# Mini_System.net
KiCad netlist of a schematic drawn in Altium Designer
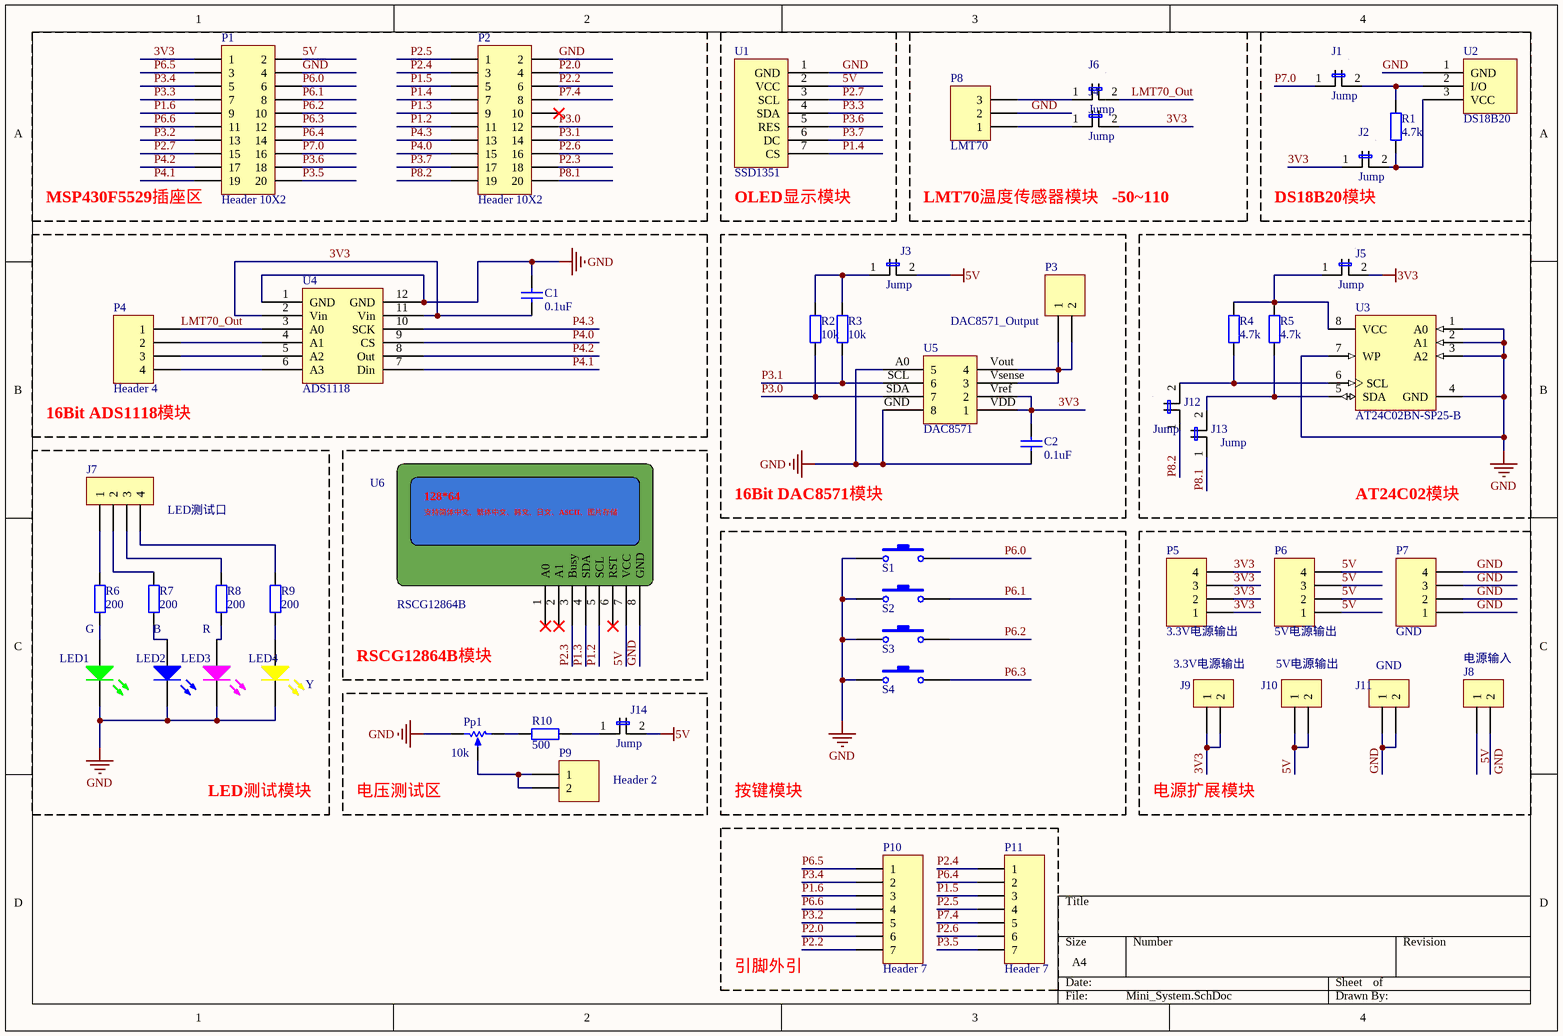
[diagram p0: Mini_System.SchDoc]

(export (version "E")
  (design (tool "Eeschema 10.0.6"))
  (components
    (comp (ref "C1")
      (value "0.1uF")
      (footprint "Capacitor-Disk-Middle")
      (description "CBB聚乙烯薄膜电容")
      (fields (field (name "VOLTAGE") "63V") (field (name "PUBLISHER") "Altium Limited"))
      (libsource (lib "02-Miscellaneous_Devices_ZSF_Library") (part "Cap Nicklon"))
    )
    (comp (ref "C2")
      (value "0.1uF")
      (footprint "Capacitor-Disk-Middle")
      (description "CBB聚乙烯薄膜电容")
      (fields (field (name "VOLTAGE") "63V") (field (name "PUBLISHER") "Altium Limited"))
      (libsource (lib "02-Miscellaneous_Devices_ZSF_Library") (part "Cap Nicklon"))
    )
    (comp (ref "J1") (value "Jump") (footprint "HDR-1x2") (libsource (lib "Mini_System") (part "Jump")))
    (comp (ref "J2") (value "Jump") (footprint "HDR-1x2") (libsource (lib "Mini_System") (part "Jump")))
    (comp (ref "J3") (value "Jump") (footprint "HDR-1x2") (libsource (lib "Mini_System") (part "Jump")))
    (comp (ref "J4") (value "Jump") (footprint "HDR-1x2") (libsource (lib "Mini_System") (part "Jump")))
    (comp (ref "J5") (value "Jump") (footprint "HDR-1x2") (libsource (lib "Mini_System") (part "Jump")))
    (comp (ref "J6") (value "Jump") (footprint "HDR-1x2") (libsource (lib "Mini_System") (part "Jump")))
    (comp (ref "J7")
      (value "LED测试口")
      (footprint "HDR-1X4_M")
      (description "排针")
      (libsource (lib "Connector") (part "HDR1X4"))
    )
    (comp (ref "J8")
      (value "电源输入")
      (footprint "Connector:XH2.54-2P")
      (description "连接器")
      (libsource (lib "Connector") (part "CON2"))
    )
    (comp (ref "J9")
      (value "3.3V电源输出")
      (footprint "Connector:WJ500V-5.08-2")
      (description "接线端子")
      (libsource (lib "Connector") (part "KF128-5.08MM-2P"))
    )
    (comp (ref "J10")
      (value "5V电源输出")
      (footprint "Connector:WJ500V-5.08-2")
      (description "接线端子")
      (libsource (lib "Connector") (part "KF128-5.08MM-2P"))
    )
    (comp (ref "J11")
      (value "GND")
      (footprint "Connector:WJ500V-5.08-2")
      (description "接线端子")
      (libsource (lib "Connector") (part "KF128-5.08MM-2P"))
    )
    (comp (ref "J12") (value "Jump") (footprint "HDR-1x2") (libsource (lib "Mini_System") (part "Jump")))
    (comp (ref "J13") (value "Jump") (footprint "HDR-1x2") (libsource (lib "Mini_System") (part "Jump")))
    (comp (ref "J14") (value "Jump") (footprint "HDR-1x2") (libsource (lib "Mini_System") (part "Jump")))
    (comp (ref "LED1")
      (value "G")
      (footprint "LED-R3-H5-SINGLE-G")
      (description "Typical INFRARED GaAs LED")
      (fields (field (name "PUBLISHER") "Altium Limited"))
      (libsource (lib "03-EButterflyIntegratedLibrary") (part "LED-3-G"))
    )
    (comp (ref "LED2")
      (value "B")
      (footprint "LED-R3-H5-SINGLE-B")
      (description "Typical INFRARED GaAs LED")
      (fields (field (name "PUBLISHER") "Altium Limited"))
      (libsource (lib "03-EButterflyIntegratedLibrary") (part "LED-3-B"))
    )
    (comp (ref "LED3")
      (value "R")
      (footprint "LED-R3-H5-SINGLE-R")
      (description "Typical INFRARED GaAs LED")
      (fields (field (name "PUBLISHER") "Altium Limited"))
      (libsource (lib "03-EButterflyIntegratedLibrary") (part "LED-3-R"))
    )
    (comp (ref "LED4")
      (value "Y")
      (footprint "LED-R3-H5-SINGLE-Y")
      (description "Typical INFRARED GaAs LED")
      (fields (field (name "PUBLISHER") "Altium Limited"))
      (libsource (lib "03-EButterflyIntegratedLibrary") (part "LED-3-Y"))
    )
    (comp (ref "P1")
      (value "Header 10X2")
      (footprint "HDR2X10")
      (description "Header, 10-Pin, Dual row")
      (fields (field (name "PUBLISHER") "Altium Limited"))
      (libsource (lib "03-EButterflyIntegratedLibrary") (part "Header 10X2"))
    )
    (comp (ref "P2")
      (value "Header 10X2")
      (footprint "HDR2X10")
      (description "Header, 10-Pin, Dual row")
      (fields (field (name "PUBLISHER") "Altium Limited"))
      (libsource (lib "03-EButterflyIntegratedLibrary") (part "Header 10X2"))
    )
    (comp (ref "P3")
      (value "DAC8571_Output")
      (footprint "HDR-1X2_H")
      (description "Header, 2-Pin")
      (fields (field (name "PUBLISHER") "Altium Limited"))
      (libsource (lib "") (part "Header 2_1"))
    )
    (comp (ref "P4")
      (value "Header 4")
      (footprint "HDR1X4")
      (description "Header, 4-Pin")
      (fields (field (name "PUBLISHER") "Altium Limited"))
      (libsource (lib "") (part "Header 4_1"))
    )
    (comp (ref "P5")
      (value "3.3V电源输出")
      (footprint "HDR1X4")
      (description "Header, 4-Pin")
      (fields (field (name "PUBLISHER") "Altium Limited"))
      (libsource (lib "03-EButterflyIntegratedLibrary") (part "Header 4"))
    )
    (comp (ref "P6")
      (value "5V电源输出")
      (footprint "HDR1X4")
      (description "Header, 4-Pin")
      (fields (field (name "PUBLISHER") "Altium Limited"))
      (libsource (lib "03-EButterflyIntegratedLibrary") (part "Header 4"))
    )
    (comp (ref "P7")
      (value "GND")
      (footprint "HDR1X4")
      (description "Header, 4-Pin")
      (fields (field (name "PUBLISHER") "Altium Limited"))
      (libsource (lib "03-EButterflyIntegratedLibrary") (part "Header 4"))
    )
    (comp (ref "P8")
      (value "LMT70")
      (footprint "HDR-1X3_M")
      (description "Header, 3-Pin")
      (fields (field (name "PUBLISHER") "Altium Limited"))
      (libsource (lib "03-EButterflyIntegratedLibrary") (part "Header 3"))
    )
    (comp (ref "P9")
      (value "Header 2")
      (footprint "HDR1X2")
      (description "Header, 2-Pin")
      (fields (field (name "PUBLISHER") "Altium Limited"))
      (libsource (lib "03-EButterflyIntegratedLibrary") (part "Header 2"))
    )
    (comp (ref "P10")
      (value "Header 7")
      (footprint "HDR-1X7_M")
      (description "Header, 7-Pin")
      (fields (field (name "PUBLISHER") "Altium Limited"))
      (libsource (lib "Miscellaneous Connectors") (part "Header 7"))
    )
    (comp (ref "P11")
      (value "Header 7")
      (footprint "HDR-1X7_M")
      (description "Header, 7-Pin")
      (fields (field (name "PUBLISHER") "Altium Limited"))
      (libsource (lib "Miscellaneous Connectors") (part "Header 7"))
    )
    (comp (ref "Pp1")
      (value "10k")
      (footprint "RP_3296")
      (description "3296电位器")
      (libsource (lib "02-Miscellaneous_Devices_ZSF_Library") (part "RP_3296"))
    )
    (comp (ref "R1")
      (value "4.7k")
      (footprint "Resistors:RS 1/4W")
      (description "Resistor")
      (fields (field (name "PUBLISHER") "Altium Limited"))
      (libsource (lib "Miscellaneous Devices") (part "Res2"))
    )
    (comp (ref "R2")
      (value "10k")
      (footprint "Resistors:RS 1/4W")
      (description "Resistor")
      (fields (field (name "PUBLISHER") "Altium Limited"))
      (libsource (lib "Miscellaneous Devices") (part "Res2"))
    )
    (comp (ref "R3")
      (value "10k")
      (footprint "Resistors:RS 1/4W")
      (description "Resistor")
      (fields (field (name "PUBLISHER") "Altium Limited"))
      (libsource (lib "Miscellaneous Devices") (part "Res2"))
    )
    (comp (ref "R4")
      (value "4.7k")
      (footprint "Resistors:RS 1/4W")
      (description "Resistor")
      (fields (field (name "PUBLISHER") "Altium Limited"))
      (libsource (lib "Miscellaneous Devices") (part "Res2"))
    )
    (comp (ref "R5")
      (value "4.7k")
      (footprint "Resistors:RS 1/4W")
      (description "Resistor")
      (fields (field (name "PUBLISHER") "Altium Limited"))
      (libsource (lib "Miscellaneous Devices") (part "Res2"))
    )
    (comp (ref "R6")
      (value "200")
      (footprint "Resistors:RS 1/4W")
      (description "Resistor")
      (fields (field (name "PUBLISHER") "Altium Limited"))
      (libsource (lib "Miscellaneous Devices") (part "Res2"))
    )
    (comp (ref "R7")
      (value "200")
      (footprint "Resistors:RS 1/4W")
      (description "Resistor")
      (fields (field (name "PUBLISHER") "Altium Limited"))
      (libsource (lib "Miscellaneous Devices") (part "Res2"))
    )
    (comp (ref "R8")
      (value "200")
      (footprint "Resistors:RS 1/4W")
      (description "Resistor")
      (fields (field (name "PUBLISHER") "Altium Limited"))
      (libsource (lib "Miscellaneous Devices") (part "Res2"))
    )
    (comp (ref "R9")
      (value "200")
      (footprint "Resistors:RS 1/4W")
      (description "Resistor")
      (fields (field (name "PUBLISHER") "Altium Limited"))
      (libsource (lib "Miscellaneous Devices") (part "Res2"))
    )
    (comp (ref "R10")
      (value "500")
      (footprint "Resistors:RS 1/4W")
      (description "Resistor")
      (fields (field (name "PUBLISHER") "Altium Limited"))
      (libsource (lib "") (part "Res2_1"))
    )
    (comp (ref "S1")
      (value "S1")
      (footprint "BUTTON_6*6")
      (description "Tactile Switch触觉开关")
      (fields (field (name "PUBLISHER") "Altium Limited"))
      (libsource (lib "02-Miscellaneous_Devices_ZSF_Library") (part "SW-PB"))
    )
    (comp (ref "S2")
      (value "S2")
      (footprint "BUTTON_6*6")
      (description "Tactile Switch触觉开关")
      (fields (field (name "PUBLISHER") "Altium Limited"))
      (libsource (lib "02-Miscellaneous_Devices_ZSF_Library") (part "SW-PB"))
    )
    (comp (ref "S3")
      (value "S3")
      (footprint "BUTTON_6*6")
      (description "Tactile Switch触觉开关")
      (fields (field (name "PUBLISHER") "Altium Limited"))
      (libsource (lib "02-Miscellaneous_Devices_ZSF_Library") (part "SW-PB"))
    )
    (comp (ref "S4")
      (value "S4")
      (footprint "BUTTON_6*6")
      (description "Tactile Switch触觉开关")
      (fields (field (name "PUBLISHER") "Altium Limited"))
      (libsource (lib "02-Miscellaneous_Devices_ZSF_Library") (part "SW-PB"))
    )
    (comp (ref "U1")
      (value "SSD1351")
      (footprint "HDR-1X7_M")
      (description "1.5寸彩色OLED")
      (libsource (lib "Mini_System") (part "1.5'OLED RGB SSD1351"))
    )
    (comp (ref "U2")
      (value "DS18B20")
      (footprint "HDR-1X3_Y")
      (libsource (lib "02-Miscellaneous_Devices_ZSF_Library") (part "DS18B20"))
    )
    (comp (ref "U3")
      (value "AT24C02BN-SP25-B")
      (footprint "DIP8-300_MH")
      (fields (field (name "PUBLISHER") "Altium Limited"))
      (libsource (lib "altium-import") (part "root_0_mirrored_AT24C02BN-SP25-B_"))
    )
    (comp (ref "U4")
      (value "ADS1118")
      (footprint "dip12")
      (description "16位ADC芯片，将模拟电压信号转化为数字信号供单片机处理")
      (libsource (lib "Mini_System") (part "ADS1118"))
    )
    (comp (ref "U5")
      (value "DAC8571")
      (footprint "DIP8-300_MH")
      (description "16位DAC芯片，将数字量转化为模拟电压输出")
      (libsource (lib "Mini_System") (part "DAC8571"))
    )
    (comp (ref "U6")
      (value "RSCG12864B")
      (footprint "HDR-1X8_M")
      (libsource (lib "Mini_System") (part "RSCG12864B"))
    )
  )
  (nets
    (net (code "1") (name "/LMT70_Out") (class "Default")
      (node (ref "J6") (pin "2") (pinfunction "2_2") (pintype "passive"))
      (node (ref "P4") (pin "1") (pinfunction "1_1") (pintype "passive"))
      (node (ref "U4") (pin "3") (pinfunction "A0_3") (pintype "passive"))
    )
    (net (code "2") (name "/P1.2") (class "Default")
      (node (ref "P2") (pin "11") (pinfunction "11_11") (pintype "passive"))
      (node (ref "U6") (pin "5") (pinfunction "SCL_5") (pintype "passive"))
    )
    (net (code "3") (name "/P1.3") (class "Default")
      (node (ref "P2") (pin "9") (pinfunction "9_9") (pintype "passive"))
      (node (ref "U6") (pin "4") (pinfunction "SDA_4") (pintype "passive"))
    )
    (net (code "4") (name "/P1.4") (class "Default")
      (node (ref "P2") (pin "7") (pinfunction "7_7") (pintype "passive"))
      (node (ref "U1") (pin "7") (pinfunction "CS_7") (pintype "passive"))
    )
    (net (code "5") (name "/P1.5") (class "Default")
      (node (ref "P11") (pin "3") (pinfunction "3_3") (pintype "passive"))
      (node (ref "P2") (pin "5") (pinfunction "5_5") (pintype "passive"))
    )
    (net (code "6") (name "/P1.6") (class "Default")
      (node (ref "P1") (pin "9") (pinfunction "9_9") (pintype "passive"))
      (node (ref "P10") (pin "3") (pinfunction "3_3") (pintype "passive"))
    )
    (net (code "7") (name "/P2.0") (class "Default")
      (node (ref "P10") (pin "6") (pinfunction "6_6") (pintype "passive"))
      (node (ref "P2") (pin "4") (pinfunction "4_4") (pintype "passive"))
    )
    (net (code "8") (name "/P2.2") (class "Default")
      (node (ref "P10") (pin "7") (pinfunction "7_7") (pintype "passive"))
      (node (ref "P2") (pin "6") (pinfunction "6_6") (pintype "passive"))
    )
    (net (code "9") (name "/P2.3") (class "Default")
      (node (ref "P2") (pin "18") (pinfunction "18_18") (pintype "passive"))
      (node (ref "U6") (pin "3") (pinfunction "Busy_3") (pintype "passive"))
    )
    (net (code "10") (name "/P2.4") (class "Default")
      (node (ref "P11") (pin "1") (pinfunction "1_1") (pintype "passive"))
      (node (ref "P2") (pin "3") (pinfunction "3_3") (pintype "passive"))
    )
    (net (code "11") (name "/P2.5") (class "Default")
      (node (ref "P11") (pin "4") (pinfunction "4_4") (pintype "passive"))
      (node (ref "P2") (pin "1") (pinfunction "1_1") (pintype "passive"))
    )
    (net (code "12") (name "/P2.6") (class "Default")
      (node (ref "P11") (pin "6") (pinfunction "6_6") (pintype "passive"))
      (node (ref "P2") (pin "16") (pinfunction "16_16") (pintype "passive"))
    )
    (net (code "13") (name "/P2.7") (class "Default")
      (node (ref "P1") (pin "15") (pinfunction "15_15") (pintype "passive"))
      (node (ref "U1") (pin "3") (pinfunction "SCL_3") (pintype "passive"))
    )
    (net (code "14") (name "/P3.0") (class "Default")
      (node (ref "P2") (pin "12") (pinfunction "12_12") (pintype "passive"))
      (node (ref "R2") (pin "1") (pinfunction "1_1") (pintype "passive"))
      (node (ref "U5") (pin "SDA") (pinfunction "7_SDA") (pintype "passive"))
    )
    (net (code "15") (name "/P3.1") (class "Default")
      (node (ref "P2") (pin "14") (pinfunction "14_14") (pintype "passive"))
      (node (ref "R3") (pin "1") (pinfunction "1_1") (pintype "passive"))
      (node (ref "U5") (pin "SCL") (pinfunction "6_SCL") (pintype "passive"))
    )
    (net (code "16") (name "/P3.2") (class "Default")
      (node (ref "P1") (pin "13") (pinfunction "13_13") (pintype "passive"))
      (node (ref "P10") (pin "5") (pinfunction "5_5") (pintype "passive"))
    )
    (net (code "17") (name "/P3.3") (class "Default")
      (node (ref "P1") (pin "7") (pinfunction "7_7") (pintype "passive"))
      (node (ref "U1") (pin "4") (pinfunction "SDA_4") (pintype "passive"))
    )
    (net (code "18") (name "/P3.4") (class "Default")
      (node (ref "P1") (pin "5") (pinfunction "5_5") (pintype "passive"))
      (node (ref "P10") (pin "2") (pinfunction "2_2") (pintype "passive"))
    )
    (net (code "19") (name "/P3.5") (class "Default")
      (node (ref "P1") (pin "20") (pinfunction "20_20") (pintype "passive"))
      (node (ref "P11") (pin "7") (pinfunction "7_7") (pintype "passive"))
    )
    (net (code "20") (name "/P3.6") (class "Default")
      (node (ref "P1") (pin "18") (pinfunction "18_18") (pintype "passive"))
      (node (ref "U1") (pin "5") (pinfunction "RES_5") (pintype "passive"))
    )
    (net (code "21") (name "/P3.7") (class "Default")
      (node (ref "P2") (pin "17") (pinfunction "17_17") (pintype "passive"))
      (node (ref "U1") (pin "6") (pinfunction "DC_6") (pintype "passive"))
    )
    (net (code "22") (name "/P4.0") (class "Default")
      (node (ref "P2") (pin "15") (pinfunction "15_15") (pintype "passive"))
      (node (ref "U4") (pin "9") (pinfunction "CS_9") (pintype "passive"))
    )
    (net (code "23") (name "/P4.1") (class "Default")
      (node (ref "P1") (pin "19") (pinfunction "19_19") (pintype "passive"))
      (node (ref "U4") (pin "7") (pinfunction "Din_7") (pintype "passive"))
    )
    (net (code "24") (name "/P4.2") (class "Default")
      (node (ref "P1") (pin "17") (pinfunction "17_17") (pintype "passive"))
      (node (ref "U4") (pin "8") (pinfunction "Out_8") (pintype "passive"))
    )
    (net (code "25") (name "/P4.3") (class "Default")
      (node (ref "P2") (pin "13") (pinfunction "13_13") (pintype "passive"))
      (node (ref "U4") (pin "10") (pinfunction "SCK_10") (pintype "passive"))
    )
    (net (code "26") (name "/P6.0") (class "Default")
      (node (ref "P1") (pin "6") (pinfunction "6_6") (pintype "passive"))
      (node (ref "S1") (pin "2") (pinfunction "2_2") (pintype "passive"))
    )
    (net (code "27") (name "/P6.1") (class "Default")
      (node (ref "P1") (pin "8") (pinfunction "8_8") (pintype "passive"))
      (node (ref "S2") (pin "2") (pinfunction "2_2") (pintype "passive"))
    )
    (net (code "28") (name "/P6.2") (class "Default")
      (node (ref "P1") (pin "10") (pinfunction "10_10") (pintype "passive"))
      (node (ref "S3") (pin "2") (pinfunction "2_2") (pintype "passive"))
    )
    (net (code "29") (name "/P6.3") (class "Default")
      (node (ref "P1") (pin "12") (pinfunction "12_12") (pintype "passive"))
      (node (ref "S4") (pin "2") (pinfunction "2_2") (pintype "passive"))
    )
    (net (code "30") (name "/P6.4") (class "Default")
      (node (ref "P1") (pin "14") (pinfunction "14_14") (pintype "passive"))
      (node (ref "P11") (pin "2") (pinfunction "2_2") (pintype "passive"))
    )
    (net (code "31") (name "/P6.5") (class "Default")
      (node (ref "P1") (pin "3") (pinfunction "3_3") (pintype "passive"))
      (node (ref "P10") (pin "1") (pinfunction "1_1") (pintype "passive"))
    )
    (net (code "32") (name "/P6.6") (class "Default")
      (node (ref "P1") (pin "11") (pinfunction "11_11") (pintype "passive"))
      (node (ref "P10") (pin "4") (pinfunction "4_4") (pintype "passive"))
    )
    (net (code "33") (name "/P7.0") (class "Default")
      (node (ref "J1") (pin "1") (pinfunction "1_1") (pintype "passive"))
      (node (ref "P1") (pin "16") (pinfunction "16_16") (pintype "passive"))
    )
    (net (code "34") (name "/P7.4") (class "Default")
      (node (ref "P11") (pin "5") (pinfunction "5_5") (pintype "passive"))
      (node (ref "P2") (pin "8") (pinfunction "8_8") (pintype "passive"))
    )
    (net (code "35") (name "/P8.1") (class "Default")
      (node (ref "J13") (pin "1") (pinfunction "1_1") (pintype "passive"))
      (node (ref "P2") (pin "20") (pinfunction "20_20") (pintype "passive"))
    )
    (net (code "36") (name "/P8.2") (class "Default")
      (node (ref "J12") (pin "1") (pinfunction "1_1") (pintype "passive"))
      (node (ref "P2") (pin "19") (pinfunction "19_19") (pintype "passive"))
    )
    (net (code "37") (name "3V3") (class "Default")
      (node (ref "C1") (pin "1") (pinfunction "1_1") (pintype "passive"))
      (node (ref "C2") (pin "2") (pinfunction "2_2") (pintype "passive"))
      (node (ref "J2") (pin "1") (pinfunction "1_1") (pintype "passive"))
      (node (ref "J4") (pin "2") (pinfunction "2_2") (pintype "passive"))
      (node (ref "J5") (pin "2") (pinfunction "2_2") (pintype "passive"))
      (node (ref "J9") (pin "1") (pinfunction "1_1") (pintype "passive"))
      (node (ref "J9") (pin "2") (pinfunction "2_2") (pintype "passive"))
      (node (ref "P1") (pin "1") (pinfunction "1_1") (pintype "passive"))
      (node (ref "P5") (pin "1") (pinfunction "1_1") (pintype "passive"))
      (node (ref "P5") (pin "2") (pinfunction "2_2") (pintype "passive"))
      (node (ref "P5") (pin "3") (pinfunction "3_3") (pintype "passive"))
      (node (ref "P5") (pin "4") (pinfunction "4_4") (pintype "passive"))
      (node (ref "U4") (pin "11") (pinfunction "Vin_11") (pintype "passive"))
      (node (ref "U4") (pin "2") (pinfunction "Vin_2") (pintype "passive"))
      (node (ref "U5") (pin "VDD") (pinfunction "1_VDD") (pintype "passive"))
      (node (ref "U5") (pin "Vref") (pinfunction "2_Vref") (pintype "passive"))
    )
    (net (code "38") (name "5V") (class "Default")
      (node (ref "J10") (pin "1") (pinfunction "1_1") (pintype "passive"))
      (node (ref "J10") (pin "2") (pinfunction "2_2") (pintype "passive"))
      (node (ref "J14") (pin "2") (pinfunction "2_2") (pintype "passive"))
      (node (ref "J3") (pin "2") (pinfunction "2_2") (pintype "passive"))
      (node (ref "J8") (pin "1") (pinfunction "1_1") (pintype "passive"))
      (node (ref "P1") (pin "2") (pinfunction "2_2") (pintype "passive"))
      (node (ref "P6") (pin "1") (pinfunction "1_1") (pintype "passive"))
      (node (ref "P6") (pin "2") (pinfunction "2_2") (pintype "passive"))
      (node (ref "P6") (pin "3") (pinfunction "3_3") (pintype "passive"))
      (node (ref "P6") (pin "4") (pinfunction "4_4") (pintype "passive"))
      (node (ref "U1") (pin "2") (pinfunction "VCC_2") (pintype "passive"))
      (node (ref "U6") (pin "7") (pinfunction "VCC_7") (pintype "passive"))
    )
    (net (code "39") (name "GND") (class "Default")
      (node (ref "C1") (pin "2") (pinfunction "2_2") (pintype "passive"))
      (node (ref "C2") (pin "1") (pinfunction "1_1") (pintype "passive"))
      (node (ref "J11") (pin "1") (pinfunction "1_1") (pintype "passive"))
      (node (ref "J11") (pin "2") (pinfunction "2_2") (pintype "passive"))
      (node (ref "J8") (pin "2") (pinfunction "2_2") (pintype "passive"))
      (node (ref "LED1") (pin "2") (pinfunction "K_2") (pintype "passive"))
      (node (ref "LED2") (pin "2") (pinfunction "K_2") (pintype "passive"))
      (node (ref "LED3") (pin "2") (pinfunction "K_2") (pintype "passive"))
      (node (ref "LED4") (pin "2") (pinfunction "K_2") (pintype "passive"))
      (node (ref "P1") (pin "4") (pinfunction "4_4") (pintype "passive"))
      (node (ref "P2") (pin "2") (pinfunction "2_2") (pintype "passive"))
      (node (ref "P7") (pin "1") (pinfunction "1_1") (pintype "passive"))
      (node (ref "P7") (pin "2") (pinfunction "2_2") (pintype "passive"))
      (node (ref "P7") (pin "3") (pinfunction "3_3") (pintype "passive"))
      (node (ref "P7") (pin "4") (pinfunction "4_4") (pintype "passive"))
      (node (ref "P8") (pin "2") (pinfunction "2_2") (pintype "passive"))
      (node (ref "Pp1") (pin "3") (pinfunction "BOT_3") (pintype "passive"))
      (node (ref "S1") (pin "1") (pinfunction "1_1") (pintype "passive"))
      (node (ref "S2") (pin "1") (pinfunction "1_1") (pintype "passive"))
      (node (ref "S3") (pin "1") (pinfunction "1_1") (pintype "passive"))
      (node (ref "S4") (pin "1") (pinfunction "1_1") (pintype "passive"))
      (node (ref "U1") (pin "1") (pinfunction "GND_1") (pintype "passive"))
      (node (ref "U2") (pin "1") (pinfunction "GND_1") (pintype "passive"))
      (node (ref "U3") (pin "1") (pinfunction "A0_1") (pintype "input"))
      (node (ref "U3") (pin "2") (pinfunction "A1_2") (pintype "input"))
      (node (ref "U3") (pin "3") (pinfunction "A2_3") (pintype "input"))
      (node (ref "U3") (pin "4") (pinfunction "GND_4") (pintype "power_in"))
      (node (ref "U3") (pin "7") (pinfunction "WP_7") (pintype "input"))
      (node (ref "U4") (pin "1") (pinfunction "GND_1") (pintype "passive"))
      (node (ref "U4") (pin "12") (pinfunction "GND_12") (pintype "passive"))
      (node (ref "U5") (pin "A0") (pinfunction "5_A0") (pintype "passive"))
      (node (ref "U5") (pin "GND") (pinfunction "8_GND") (pintype "passive"))
      (node (ref "U6") (pin "8") (pinfunction "GND_8") (pintype "passive"))
    )
    (net (code "40") (name "Net-(J3-Pad1)") (class "Default")
      (node (ref "J3") (pin "1") (pinfunction "1_1") (pintype "passive"))
      (node (ref "R2") (pin "2") (pinfunction "2_2") (pintype "passive"))
      (node (ref "R3") (pin "2") (pinfunction "2_2") (pintype "passive"))
    )
    (net (code "41") (name "Net-(J4-Pad1)") (class "Default")
      (node (ref "J4") (pin "1") (pinfunction "1_1") (pintype "passive"))
      (node (ref "P8") (pin "1") (pinfunction "1_1") (pintype "passive"))
    )
    (net (code "42") (name "Net-(J6-Pad1)") (class "Default")
      (node (ref "J6") (pin "1") (pinfunction "1_1") (pintype "passive"))
      (node (ref "P8") (pin "3") (pinfunction "3_3") (pintype "passive"))
    )
    (net (code "43") (name "Net-(J7-Pad1)") (class "Default")
      (node (ref "J7") (pin "1") (pinfunction "1_1") (pintype "passive"))
      (node (ref "R6") (pin "2") (pinfunction "2_2") (pintype "passive"))
    )
    (net (code "44") (name "Net-(J7-Pad2)") (class "Default")
      (node (ref "J7") (pin "2") (pinfunction "2_2") (pintype "passive"))
      (node (ref "R7") (pin "2") (pinfunction "2_2") (pintype "passive"))
    )
    (net (code "45") (name "Net-(J7-Pad3)") (class "Default")
      (node (ref "J7") (pin "3") (pinfunction "3_3") (pintype "passive"))
      (node (ref "R8") (pin "2") (pinfunction "2_2") (pintype "passive"))
    )
    (net (code "46") (name "Net-(J7-Pad4)") (class "Default")
      (node (ref "J7") (pin "4") (pinfunction "4_4") (pintype "passive"))
      (node (ref "R9") (pin "2") (pinfunction "2_2") (pintype "passive"))
    )
    (net (code "47") (name "Net-(J14-Pad1)") (class "Default")
      (node (ref "J14") (pin "1") (pinfunction "1_1") (pintype "passive"))
      (node (ref "R10") (pin "1") (pinfunction "1_1") (pintype "passive"))
    )
    (net (code "48") (name "Net-(LED1-A)") (class "Default")
      (node (ref "LED1") (pin "1") (pinfunction "A_1") (pintype "passive"))
      (node (ref "R6") (pin "1") (pinfunction "1_1") (pintype "passive"))
    )
    (net (code "49") (name "Net-(LED2-A)") (class "Default")
      (node (ref "LED2") (pin "1") (pinfunction "A_1") (pintype "passive"))
      (node (ref "R7") (pin "1") (pinfunction "1_1") (pintype "passive"))
    )
    (net (code "50") (name "Net-(LED3-A)") (class "Default")
      (node (ref "LED3") (pin "1") (pinfunction "A_1") (pintype "passive"))
      (node (ref "R8") (pin "1") (pinfunction "1_1") (pintype "passive"))
    )
    (net (code "51") (name "Net-(LED4-A)") (class "Default")
      (node (ref "LED4") (pin "1") (pinfunction "A_1") (pintype "passive"))
      (node (ref "R9") (pin "1") (pinfunction "1_1") (pintype "passive"))
    )
    (net (code "52") (name "Net-(Pp1-TAP)") (class "Default")
      (node (ref "P9") (pin "1") (pinfunction "1_1") (pintype "passive"))
      (node (ref "P9") (pin "2") (pinfunction "2_2") (pintype "passive"))
      (node (ref "Pp1") (pin "2") (pinfunction "TAP_2") (pintype "passive"))
    )
    (net (code "53") (name "Net-(Pp1-TOP)") (class "Default")
      (node (ref "Pp1") (pin "1") (pinfunction "TOP_1") (pintype "passive"))
      (node (ref "R10") (pin "2") (pinfunction "2_2") (pintype "passive"))
    )
    (net (code "54") (name "Net-(U2-I{slash}O)") (class "Default")
      (node (ref "J1") (pin "2") (pinfunction "2_2") (pintype "passive"))
      (node (ref "R1") (pin "2") (pinfunction "2_2") (pintype "passive"))
      (node (ref "U2") (pin "2") (pinfunction "I/O_2") (pintype "passive"))
    )
    (net (code "55") (name "Net-(U2-VCC)") (class "Default")
      (node (ref "J2") (pin "2") (pinfunction "2_2") (pintype "passive"))
      (node (ref "R1") (pin "1") (pinfunction "1_1") (pintype "passive"))
      (node (ref "U2") (pin "3") (pinfunction "VCC_3") (pintype "passive"))
    )
    (net (code "56") (name "Net-(U3-SCL)") (class "Default")
      (node (ref "J12") (pin "2") (pinfunction "2_2") (pintype "passive"))
      (node (ref "R4") (pin "1") (pinfunction "1_1") (pintype "passive"))
      (node (ref "U3") (pin "6") (pinfunction "SCL_6") (pintype "input"))
    )
    (net (code "57") (name "Net-(U3-SDA)") (class "Default")
      (node (ref "J13") (pin "2") (pinfunction "2_2") (pintype "passive"))
      (node (ref "R5") (pin "1") (pinfunction "1_1") (pintype "passive"))
      (node (ref "U3") (pin "5") (pinfunction "SDA_5") (pintype "bidirectional"))
    )
    (net (code "58") (name "Net-(U3-VCC)") (class "Default")
      (node (ref "J5") (pin "1") (pinfunction "1_1") (pintype "passive"))
      (node (ref "R4") (pin "2") (pinfunction "2_2") (pintype "passive"))
      (node (ref "R5") (pin "2") (pinfunction "2_2") (pintype "passive"))
      (node (ref "U3") (pin "8") (pinfunction "VCC_8") (pintype "power_in"))
    )
    (net (code "59") (name "Net-(U4-A1)") (class "Default")
      (node (ref "P4") (pin "2") (pinfunction "2_2") (pintype "passive"))
      (node (ref "U4") (pin "4") (pinfunction "A1_4") (pintype "passive"))
    )
    (net (code "60") (name "Net-(U4-A2)") (class "Default")
      (node (ref "P4") (pin "3") (pinfunction "3_3") (pintype "passive"))
      (node (ref "U4") (pin "5") (pinfunction "A2_5") (pintype "passive"))
    )
    (net (code "61") (name "Net-(U4-A3)") (class "Default")
      (node (ref "P4") (pin "4") (pinfunction "4_4") (pintype "passive"))
      (node (ref "U4") (pin "6") (pinfunction "A3_6") (pintype "passive"))
    )
    (net (code "62") (name "Net-(U5-3)") (class "Default")
      (node (ref "P3") (pin "1") (pinfunction "1_1") (pintype "passive"))
      (node (ref "P3") (pin "2") (pinfunction "2_2") (pintype "passive"))
      (node (ref "U5") (pin "Vout") (pinfunction "4_Vout") (pintype "passive"))
      (node (ref "U5") (pin "Vsense") (pinfunction "3_Vsense") (pintype "passive"))
    )
    (net (code "63") (name "unconnected-(P2-Pad10)") (class "Default")
      (node (ref "P2") (pin "10") (pinfunction "10_10") (pintype "passive+no_connect"))
    )
    (net (code "64") (name "unconnected-(U6-A0-Pad1)") (class "Default")
      (node (ref "U6") (pin "1") (pinfunction "A0_1") (pintype "passive+no_connect"))
    )
    (net (code "65") (name "unconnected-(U6-A1-Pad2)") (class "Default")
      (node (ref "U6") (pin "2") (pinfunction "A1_2") (pintype "passive+no_connect"))
    )
    (net (code "66") (name "unconnected-(U6-RST-Pad6)") (class "Default")
      (node (ref "U6") (pin "6") (pinfunction "RST_6") (pintype "passive+no_connect"))
    )
  )
)
